# Encoder3.net
KiCad netlist of a schematic drawn in Altium Designer
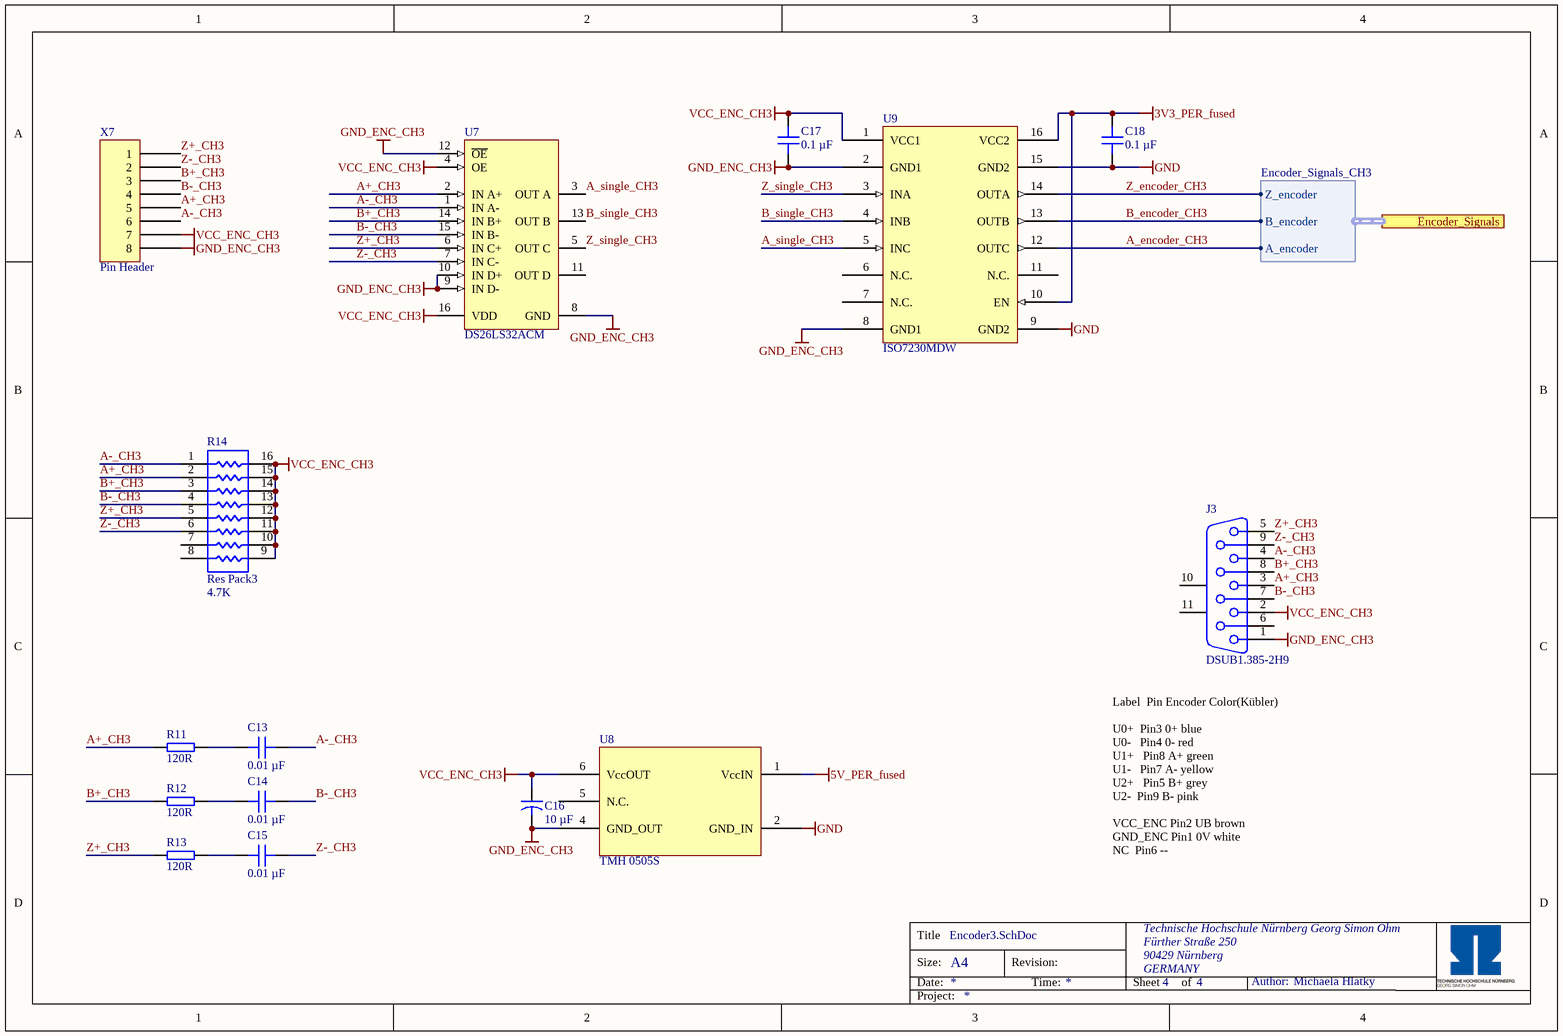
[diagram p0: Encoder3.SchDoc]

(export (version "E")
  (design (tool "Eeschema 10.0.6"))
  (components
    (comp (ref "C13")
      (value "0.01 µF")
      (footprint "C_0805")
      (description "Capacitor 0805, 100 VDC, 0.01 µF, X7R")
      (fields
        (field (name "MANUFACTURER PART NUMBER") "GRM21BR72A103KA01L")
        (field (name "MANUFACTURER") "Murata Electronics")
        (field (name "CREATED FROM") "MGremer")
      )
      (libsource (lib "user") (part "Capacitor"))
    )
    (comp (ref "C14")
      (value "0.01 µF")
      (footprint "C_0805")
      (description "Capacitor 0805, 100 VDC, 0.01 µF, X7R")
      (fields
        (field (name "MANUFACTURER PART NUMBER") "GRM21BR72A103KA01L")
        (field (name "MANUFACTURER") "Murata Electronics")
        (field (name "CREATED FROM") "MGremer")
      )
      (libsource (lib "user") (part "Capacitor"))
    )
    (comp (ref "C15")
      (value "0.01 µF")
      (footprint "C_0805")
      (description "Capacitor 0805, 100 VDC, 0.01 µF, X7R")
      (fields
        (field (name "MANUFACTURER PART NUMBER") "GRM21BR72A103KA01L")
        (field (name "MANUFACTURER") "Murata Electronics")
        (field (name "CREATED FROM") "MGremer")
      )
      (libsource (lib "user") (part "Capacitor"))
    )
    (comp (ref "C16")
      (value "10 µF")
      (footprint "CAPR5-4X5")
      (description "Capacitor; 2 Leads")
      (fields
        (field (name "MANUFACTURER PART NUMBER") "CAPR5-4X5")
        (field (name "PUBLISHER") "Altium Limited")
        (field (name "CREATED FROM") "MHlatky")
      )
      (libsource (lib "user") (part "Cap2"))
    )
    (comp (ref "C17")
      (value "0.1 µF")
      (footprint "C_0805")
      (description "Capacitor 0805, 50 VDC, 0.1 µF, X7R")
      (fields
        (field (name "MANUFACTURER PART NUMBER") "C0805C104J5RECTU")
        (field (name "MANUFACTURER") "KEMET")
        (field (name "CREATED FROM") "MGremer")
      )
      (libsource (lib "user") (part "Capacitor"))
    )
    (comp (ref "C18")
      (value "0.1 µF")
      (footprint "C_0805")
      (description "Capacitor 0805, 50 VDC, 0.1 µF, X7R")
      (fields
        (field (name "MANUFACTURER PART NUMBER") "C0805C104J5RECTU")
        (field (name "MANUFACTURER") "KEMET")
        (field (name "CREATED FROM") "MGremer")
      )
      (libsource (lib "user") (part "Capacitor"))
    )
    (comp (ref "J3")
      (value "DSUB1.385-2H9")
      (footprint "DSUB1.385-2H9")
      (description "Connector; D Subminiature; 9 Position; Right Angle; Pitch 1.385 mm")
      (fields
        (field (name "MANUFACTURER") "Altium")
        (field (name "PUBLISHER") "Altium Limited")
        (field (name "CREATED FROM") "MHlatky")
      )
      (libsource (lib "user") (part "D Connector 9"))
    )
    (comp (ref "R11")
      (value "120R")
      (footprint "RES 0603_1608")
      (description "SMD resistor E24 series")
      (fields
        (field (name "MANUFACTURER PART NUMBER") "RK73B1JTTD121J")
        (field (name "MANUFACTURER") "KOA Speer")
        (field (name "CREATED FROM") "MGremer")
      )
      (libsource (lib "user") (part "Resistor"))
    )
    (comp (ref "R12")
      (value "120R")
      (footprint "RES 0603_1608")
      (description "SMD resistor E24 series")
      (fields
        (field (name "MANUFACTURER PART NUMBER") "RK73B1JTTD121J")
        (field (name "MANUFACTURER") "KOA Speer")
        (field (name "CREATED FROM") "MGremer")
      )
      (libsource (lib "user") (part "Resistor"))
    )
    (comp (ref "R13")
      (value "120R")
      (footprint "RES 0603_1608")
      (description "SMD resistor E24 series")
      (fields
        (field (name "MANUFACTURER PART NUMBER") "RK73B1JTTD121J")
        (field (name "MANUFACTURER") "KOA Speer")
        (field (name "CREATED FROM") "MGremer")
      )
      (libsource (lib "user") (part "Resistor"))
    )
    (comp (ref "R14")
      (value "Res Pack3")
      (footprint "SO-16_N")
      (description "SOIC, 16-Leads, Body 9.9x3.9mm, Pitch 1.27mm, IPC Medium Density")
      (fields
        (field (name "ALTIUM_VALUE") "4.7K")
        (field (name "PUBLISHER") "Altium Limited")
        (field (name "CREATED FROM") "MHlatky")
      )
      (libsource (lib "user") (part "Res Pack3"))
    )
    (comp (ref "U7")
      (value "DS26LS32ACM")
      (footprint "M16A_M")
      (description "DS26LS32AC/DS26LS32C/DS26LS32M/DS26LS33M Quad Differential Line Receivers")
      (fields
        (field (name "MANUFACTURER") "Texas Instruments")
        (field (name "PUBLISHER") "Altium Limited")
        (field (name "CREATED FROM") "MHlatky")
      )
      (libsource (lib "user") (part "DS26LS32ACM"))
    )
    (comp (ref "U8")
      (value "TMH 0505S")
      (footprint "SIL-6(7)")
      (fields (field (name "MANUFACTURER") "Traco") (field (name "CREATED FROM") "MHlatky"))
      (libsource (lib "user") (part "TRACO TMH 0505S"))
    )
    (comp (ref "U9")
      (value "ISO7230MDW")
      (footprint "TI ISO7230 SOIC")
      (description "ISO723xx High-Speed, Triple-Channel Digital Isolators")
      (fields (field (name "MANUFACTURER") "Analog Devices") (field (name "CREATED FROM") "MHlatky"))
      (libsource (lib "user") (part "TI ISO7230"))
    )
    (comp (ref "X7")
      (value "Pin Header")
      (footprint "HDR1X8")
      (description "8 Pin")
      (fields (field (name "MANUFACTURER PART NUMBER") "HDR1X8") (field (name "CREATED FROM") "MHlatky"))
      (libsource (lib "user") (part "8 Pin"))
    )
  )
  (nets
    (net (code "2") (name "/A+_CH3") (class "Default")
      (node (ref "J3") (pin "3") (pinfunction "3_3") (pintype "passive"))
      (node (ref "R11") (pin "1") (pinfunction "1_1") (pintype "passive"))
      (node (ref "R14") (pin "2") (pinfunction "2_2") (pintype "passive"))
      (node (ref "U7") (pin "2") (pinfunction "IN_A+_2") (pintype "input"))
      (node (ref "X7") (pin "5") (pinfunction "5_5") (pintype "passive"))
    )
    (net (code "3") (name "/A-_CH3") (class "Default")
      (node (ref "C13") (pin "2") (pinfunction "2_2") (pintype "passive"))
      (node (ref "J3") (pin "4") (pinfunction "4_4") (pintype "passive"))
      (node (ref "R14") (pin "1") (pinfunction "1_1") (pintype "passive"))
      (node (ref "U7") (pin "1") (pinfunction "IN_A-_1") (pintype "input"))
      (node (ref "X7") (pin "6") (pinfunction "6_6") (pintype "passive"))
    )
    (net (code "4") (name "/A_encoder_CH3") (class "Default")
      (node (ref "U9") (pin "12") (pinfunction "OUTC_12") (pintype "output"))
    )
    (net (code "5") (name "/A_single_CH3") (class "Default")
      (node (ref "U7") (pin "3") (pinfunction "OUT_A_3") (pintype "tri_state"))
      (node (ref "U9") (pin "5") (pinfunction "INC_5") (pintype "input"))
    )
    (net (code "6") (name "/B+_CH3") (class "Default")
      (node (ref "J3") (pin "8") (pinfunction "8_8") (pintype "passive"))
      (node (ref "R12") (pin "1") (pinfunction "1_1") (pintype "passive"))
      (node (ref "R14") (pin "3") (pinfunction "3_3") (pintype "passive"))
      (node (ref "U7") (pin "14") (pinfunction "IN_B+_14") (pintype "input"))
      (node (ref "X7") (pin "3") (pinfunction "3_3") (pintype "passive"))
    )
    (net (code "7") (name "/B-_CH3") (class "Default")
      (node (ref "C14") (pin "2") (pinfunction "2_2") (pintype "passive"))
      (node (ref "J3") (pin "7") (pinfunction "7_7") (pintype "passive"))
      (node (ref "R14") (pin "4") (pinfunction "4_4") (pintype "passive"))
      (node (ref "U7") (pin "15") (pinfunction "IN_B-_15") (pintype "input"))
      (node (ref "X7") (pin "4") (pinfunction "4_4") (pintype "passive"))
    )
    (net (code "8") (name "/B_encoder_CH3") (class "Default")
      (node (ref "U9") (pin "13") (pinfunction "OUTB_13") (pintype "output"))
    )
    (net (code "9") (name "/B_single_CH3") (class "Default")
      (node (ref "U7") (pin "13") (pinfunction "OUT_B_13") (pintype "tri_state"))
      (node (ref "U9") (pin "4") (pinfunction "INB_4") (pintype "input"))
    )
    (net (code "10") (name "/Z+_CH3") (class "Default")
      (node (ref "J3") (pin "5") (pinfunction "5_5") (pintype "passive"))
      (node (ref "R13") (pin "1") (pinfunction "1_1") (pintype "passive"))
      (node (ref "R14") (pin "5") (pinfunction "5_5") (pintype "passive"))
      (node (ref "U7") (pin "6") (pinfunction "IN_C+_6") (pintype "input"))
      (node (ref "X7") (pin "1") (pinfunction "1_1") (pintype "passive"))
    )
    (net (code "11") (name "/Z-_CH3") (class "Default")
      (node (ref "C15") (pin "2") (pinfunction "2_2") (pintype "passive"))
      (node (ref "J3") (pin "9") (pinfunction "9_9") (pintype "passive"))
      (node (ref "R14") (pin "6") (pinfunction "6_6") (pintype "passive"))
      (node (ref "U7") (pin "7") (pinfunction "IN_C-_7") (pintype "input"))
      (node (ref "X7") (pin "2") (pinfunction "2_2") (pintype "passive"))
    )
    (net (code "12") (name "/Z_encoder_CH3") (class "Default")
      (node (ref "U9") (pin "14") (pinfunction "OUTA_14") (pintype "output"))
    )
    (net (code "13") (name "/Z_single_CH3") (class "Default")
      (node (ref "U7") (pin "5") (pinfunction "OUT_C_5") (pintype "tri_state"))
      (node (ref "U9") (pin "3") (pinfunction "INA_3") (pintype "input"))
    )
    (net (code "15") (name "3V3_PER_fused") (class "Default")
      (node (ref "C18") (pin "2") (pinfunction "2_2") (pintype "passive"))
      (node (ref "U9") (pin "10") (pinfunction "EN_10") (pintype "input"))
      (node (ref "U9") (pin "16") (pinfunction "VCC2_16") (pintype "passive"))
    )
    (net (code "16") (name "5V_PER_fused") (class "Default")
      (node (ref "U8") (pin "1") (pinfunction "VccIN_1") (pintype "passive"))
    )
    (net (code "17") (name "GND") (class "Default")
      (node (ref "C18") (pin "1") (pinfunction "1_1") (pintype "passive"))
      (node (ref "U8") (pin "2") (pinfunction "GND_IN_2") (pintype "passive"))
      (node (ref "U9") (pin "15") (pinfunction "GND2_15") (pintype "passive"))
      (node (ref "U9") (pin "9") (pinfunction "GND2_9") (pintype "passive"))
    )
    (net (code "18") (name "GND_ENC_CH3") (class "Default")
      (node (ref "C16") (pin "2") (pinfunction "2_2") (pintype "passive"))
      (node (ref "C17") (pin "1") (pinfunction "1_1") (pintype "passive"))
      (node (ref "J3") (pin "1") (pinfunction "1_1") (pintype "passive"))
      (node (ref "U7") (pin "10") (pinfunction "IN_D+_10") (pintype "input"))
      (node (ref "U7") (pin "12") (pinfunction "~{OE}_12") (pintype "input"))
      (node (ref "U7") (pin "8") (pinfunction "GND_8") (pintype "power_in"))
      (node (ref "U7") (pin "9") (pinfunction "IN_D-_9") (pintype "input"))
      (node (ref "U8") (pin "4") (pinfunction "GND_OUT_4") (pintype "passive"))
      (node (ref "U9") (pin "2") (pinfunction "GND1_2") (pintype "passive"))
      (node (ref "U9") (pin "8") (pinfunction "GND1_8") (pintype "passive"))
      (node (ref "X7") (pin "8") (pinfunction "8_8") (pintype "passive"))
    )
    (net (code "19") (name "Net-(C13-Pad1)") (class "Default")
      (node (ref "C13") (pin "1") (pinfunction "1_1") (pintype "passive"))
      (node (ref "R11") (pin "2") (pinfunction "2_2") (pintype "passive"))
    )
    (net (code "20") (name "Net-(C14-Pad1)") (class "Default")
      (node (ref "C14") (pin "1") (pinfunction "1_1") (pintype "passive"))
      (node (ref "R12") (pin "2") (pinfunction "2_2") (pintype "passive"))
    )
    (net (code "21") (name "Net-(C15-Pad1)") (class "Default")
      (node (ref "C15") (pin "1") (pinfunction "1_1") (pintype "passive"))
      (node (ref "R13") (pin "2") (pinfunction "2_2") (pintype "passive"))
    )
    (net (code "22") (name "VCC_ENC_CH3") (class "Default")
      (node (ref "C16") (pin "1") (pinfunction "1_1") (pintype "passive"))
      (node (ref "C17") (pin "2") (pinfunction "2_2") (pintype "passive"))
      (node (ref "J3") (pin "2") (pinfunction "2_2") (pintype "passive"))
      (node (ref "R14") (pin "10") (pinfunction "10_10") (pintype "passive"))
      (node (ref "R14") (pin "11") (pinfunction "11_11") (pintype "passive"))
      (node (ref "R14") (pin "12") (pinfunction "12_12") (pintype "passive"))
      (node (ref "R14") (pin "13") (pinfunction "13_13") (pintype "passive"))
      (node (ref "R14") (pin "14") (pinfunction "14_14") (pintype "passive"))
      (node (ref "R14") (pin "15") (pinfunction "15_15") (pintype "passive"))
      (node (ref "R14") (pin "16") (pinfunction "16_16") (pintype "passive"))
      (node (ref "R14") (pin "9") (pinfunction "9_9") (pintype "passive"))
      (node (ref "U7") (pin "16") (pinfunction "VDD_16") (pintype "power_in"))
      (node (ref "U7") (pin "4") (pinfunction "OE_4") (pintype "input"))
      (node (ref "U8") (pin "6") (pinfunction "VccOUT_6") (pintype "passive"))
      (node (ref "U9") (pin "1") (pinfunction "VCC1_1") (pintype "passive"))
      (node (ref "X7") (pin "7") (pinfunction "7_7") (pintype "passive"))
    )
    (net (code "23") (name "unconnected-(J3-MH1-Pad10)") (class "Default")
      (node (ref "J3") (pin "10") (pinfunction "MH1_10") (pintype "passive"))
    )
    (net (code "24") (name "unconnected-(J3-MH2-Pad11)") (class "Default")
      (node (ref "J3") (pin "11") (pinfunction "MH2_11") (pintype "passive"))
    )
    (net (code "25") (name "unconnected-(J3-Pad6)") (class "Default")
      (node (ref "J3") (pin "6") (pinfunction "6_6") (pintype "passive"))
    )
    (net (code "26") (name "unconnected-(R14-Pad7)") (class "Default")
      (node (ref "R14") (pin "7") (pinfunction "7_7") (pintype "passive"))
    )
    (net (code "27") (name "unconnected-(R14-Pad8)") (class "Default")
      (node (ref "R14") (pin "8") (pinfunction "8_8") (pintype "passive"))
    )
    (net (code "28") (name "unconnected-(U7-OUT_D-Pad11)") (class "Default")
      (node (ref "U7") (pin "11") (pinfunction "OUT_D_11") (pintype "tri_state"))
    )
    (net (code "29") (name "unconnected-(U8-N.C.-Pad5)") (class "Default")
      (node (ref "U8") (pin "5") (pinfunction "N.C._5") (pintype "passive"))
    )
    (net (code "30") (name "unconnected-(U9-N.C.-Pad6)") (class "Default")
      (node (ref "U9") (pin "6") (pinfunction "N.C._6") (pintype "passive"))
    )
    (net (code "31") (name "unconnected-(U9-N.C.-Pad7)") (class "Default")
      (node (ref "U9") (pin "7") (pinfunction "N.C._7") (pintype "passive"))
    )
    (net (code "32") (name "unconnected-(U9-N.C.-Pad11)") (class "Default")
      (node (ref "U9") (pin "11") (pinfunction "N.C._11") (pintype "passive"))
    )
  )
)
